# tapegyseg.net
KiCad netlist of a schematic drawn in Altium Designer
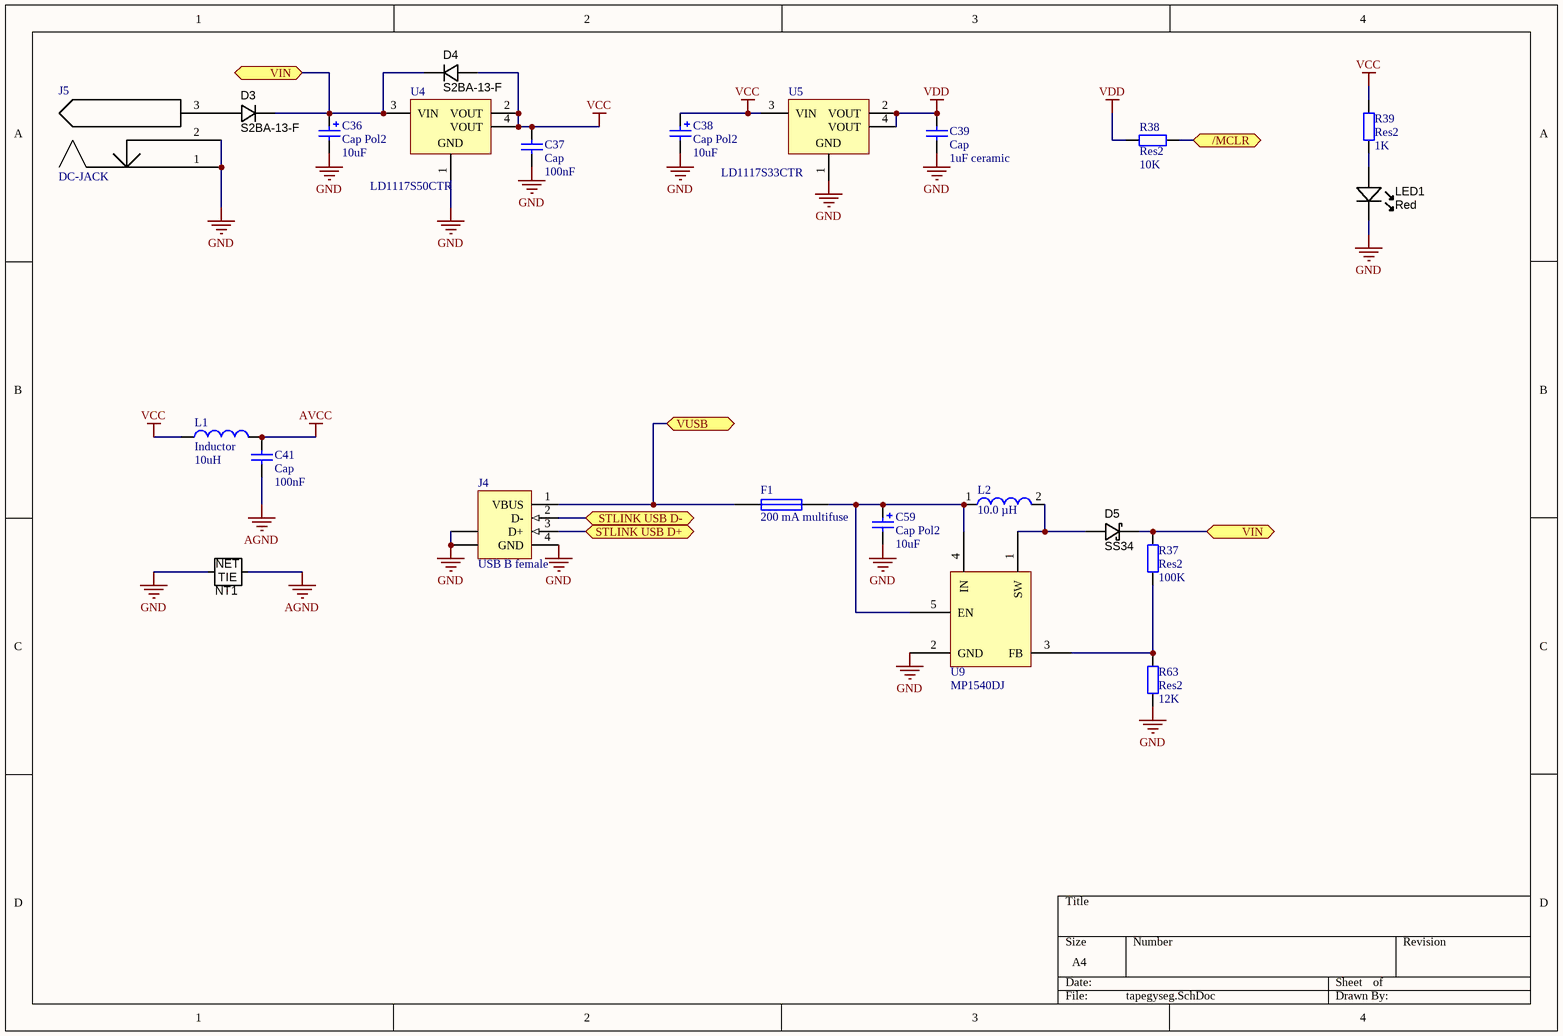
[diagram p0: tapegyseg.SchDoc]

(export (version "E")
  (design (tool "Eeschema 10.0.6"))
  (components
    (comp (ref "C36")
      (value "Cap Pol2")
      (footprint "CAPMP3528X210N")
      (description "Polarized Capacitor (Axial)")
      (fields (field (name "ALTIUM_VALUE") "10uF") (field (name "PUBLISHER") "Altium Limited"))
      (libsource (lib "Miscellaneous Devices") (part "Cap Pol2"))
    )
    (comp (ref "C37")
      (value "Cap")
      (footprint "CAPC2012X135N")
      (description "Capacitor")
      (fields (field (name "ALTIUM_VALUE") "100nF") (field (name "PUBLISHER") "Altium Limited"))
      (libsource (lib "Miscellaneous Devices") (part "Cap"))
    )
    (comp (ref "C38")
      (value "Cap Pol2")
      (footprint "CAPMP3528X210N")
      (description "Polarized Capacitor (Axial)")
      (fields (field (name "ALTIUM_VALUE") "10uF") (field (name "PUBLISHER") "Altium Limited"))
      (libsource (lib "Miscellaneous Devices") (part "Cap Pol2"))
    )
    (comp (ref "C39")
      (value "Cap")
      (footprint "CAPC2012X135N")
      (description "Capacitor")
      (fields (field (name "ALTIUM_VALUE") "1uF ceramic") (field (name "PUBLISHER") "Altium Limited"))
      (libsource (lib "Miscellaneous Devices") (part "Cap"))
    )
    (comp (ref "C41")
      (value "Cap")
      (footprint "CAPC2012X135N")
      (description "Capacitor")
      (fields (field (name "ALTIUM_VALUE") "100nF") (field (name "PUBLISHER") "Altium Limited"))
      (libsource (lib "Miscellaneous Devices") (part "Cap"))
    )
    (comp (ref "C59")
      (value "Cap Pol2")
      (footprint "CAPMP3528X210N")
      (description "Polarized Capacitor (Axial)")
      (fields (field (name "ALTIUM_VALUE") "10uF") (field (name "PUBLISHER") "Altium Limited"))
      (libsource (lib "Miscellaneous Devices") (part "Cap Pol2"))
    )
    (comp (ref "D3")
      (value "100V; 1.5A")
      (footprint "DO-214AC")
      (description "Diode SMD 100V 1.5A SMA")
      (fields (field (name "MANUFACTURER PART NUMBER 1") "S2BA-13-F"))
      (libsource (lib "PBL - Diodes") (part "DIODE_100V_1.5A_SMA"))
    )
    (comp (ref "D4")
      (value "100V; 1.5A")
      (footprint "DO-214AC")
      (description "Diode SMD 100V 1.5A SMA")
      (fields (field (name "MANUFACTURER PART NUMBER 1") "S2BA-13-F"))
      (libsource (lib "PBL - Diodes") (part "DIODE_100V_1.5A_SMA"))
    )
    (comp (ref "D5")
      (value "SS34")
      (footprint "DO-214AA")
      (description "Diode Schottky SMD 30V 2A DO-214AA")
      (libsource (lib "PBL - Diodes") (part "DIODE_SCHOTTKY_MBRS130L"))
    )
    (comp (ref "F1")
      (value "200 mA multifuse")
      (footprint "RESC6332X70N")
      (description "Fuse")
      (fields (field (name "PUBLISHER") "Altium Limited"))
      (libsource (lib "Miscellaneous Devices") (part "Fuse 1"))
    )
    (comp (ref "J4")
      (value "USB B female")
      (footprint "1437106")
      (description "USB 1.1, Right Angle, Thru-Hole, B Type, Receptacle, 4 Position, Natural")
      (fields (field (name "PUBLISHER") "Altium Limited"))
      (libsource (lib "AMP Serial Bus USB") (part "4-1437106-8"))
    )
    (comp (ref "J5")
      (value "DC-JACK")
      (footprint "JACK")
      (description "Tápcsatlakozó")
      (libsource (lib "sajat") (part "DC-JACK"))
    )
    (comp (ref "L1")
      (value "Inductor")
      (footprint "6-0805_N")
      (fields (field (name "ALTIUM_VALUE") "10uH") (field (name "PUBLISHER") "Altium Limited"))
      (libsource (lib "Miscellaneous Devices") (part "Inductor"))
    )
    (comp (ref "L2")
      (value "7447745100")
      (footprint "WE-PD2-MS")
      (description "SMD Power Inductor WE-PD2, L = 10.0 µH")
      (fields (field (name "INDUCTANCE") "10.0 µH"))
      (libsource (lib "Wuerth Elektronik SMD Power Choke") (part "7447745100"))
    )
    (comp (ref "LED1")
      (value "~")
      (footprint "LED-0805-K")
      (description "LED 0805 SMD Red 6mcd 621nm")
      (fields (field (name "COLOR") "Red"))
      (libsource (lib "PBL - Light Sources") (part "LED_SMD_Red_0805_6mcd"))
    )
    (comp (ref "NT1")
      (value "Net Tie")
      (footprint "NetTie_External_24mil")
      (libsource (lib "PBL - Pads and Jumpers") (part "JUMP_NETTIE"))
    )
    (comp (ref "R37")
      (value "Res2")
      (footprint "RESC2012X70N")
      (description "Resistor")
      (fields (field (name "ALTIUM_VALUE") "100K") (field (name "PUBLISHER") "Altium Limited"))
      (libsource (lib "") (part "Res2_1"))
    )
    (comp (ref "R38")
      (value "Res2")
      (footprint "RESC2012X70N")
      (description "Resistor")
      (fields (field (name "ALTIUM_VALUE") "10K") (field (name "PUBLISHER") "Altium Limited"))
      (libsource (lib "Miscellaneous Devices") (part "Res2"))
    )
    (comp (ref "R39")
      (value "Res2")
      (footprint "RESC2012X70N")
      (description "Resistor")
      (fields (field (name "ALTIUM_VALUE") "1K") (field (name "PUBLISHER") "Altium Limited"))
      (libsource (lib "") (part "Res2_1"))
    )
    (comp (ref "R63")
      (value "Res2")
      (footprint "RESC2012X70N")
      (description "Resistor")
      (fields (field (name "ALTIUM_VALUE") "12K") (field (name "PUBLISHER") "Altium Limited"))
      (libsource (lib "") (part "Res2_1"))
    )
    (comp (ref "U4")
      (value "LD1117S50CTR")
      (footprint "SOT-223_M")
      (description "Fixed Low Drop Positive Voltage Regulator, 5V, 4-Pin SOT-223, Tape and Reel")
      (libsource (lib "STMicroelectronics Power Management Linear Regulator") (part "LD1117S50CTR"))
    )
    (comp (ref "U5")
      (value "LD1117S33CTR")
      (footprint "SOT-223_L")
      (description "Fixed Low Drop Positive Voltage Regulator, 3.3V, 4-Pin SOT-223, Tape and Reel")
      (libsource (lib "STMicroelectronics Power Management Linear Regulator") (part "LD1117S33CTR"))
    )
    (comp (ref "U9")
      (value "MP1540DJ")
      (footprint "S5")
      (description "Step-up converter")
      (libsource (lib "sajat") (part "MP1540"))
    )
  )
  (nets
    (net (code "1") (name "/STLINK USB D+") (class "Default")
      (node (ref "J4") (pin "3") (pinfunction "D+_3") (pintype "input"))
    )
    (net (code "2") (name "/STLINK USB D-") (class "Default")
      (node (ref "J4") (pin "2") (pinfunction "D-_2") (pintype "input"))
    )
    (net (code "3") (name "/VIN") (class "Default")
      (node (ref "C36") (pin "1") (pinfunction "1_1") (pintype "passive"))
      (node (ref "D3") (pin "K") (pinfunction "K_K") (pintype "passive"))
      (node (ref "D4") (pin "K") (pinfunction "K_K") (pintype "passive"))
      (node (ref "D5") (pin "K") (pinfunction "K_K") (pintype "passive"))
      (node (ref "R37") (pin "2") (pinfunction "2_2") (pintype "passive"))
      (node (ref "U4") (pin "3") (pinfunction "VIN_3") (pintype "power_in"))
    )
    (net (code "4") (name "/VUSB") (class "Default")
      (node (ref "F1") (pin "1") (pinfunction "1_1") (pintype "passive"))
      (node (ref "J4") (pin "1") (pinfunction "VBUS_1") (pintype "power_in"))
    )
    (net (code "5") (name "/{slash}MCLR") (class "Default")
      (node (ref "R38") (pin "2") (pinfunction "2_2") (pintype "passive"))
    )
    (net (code "6") (name "AGND") (class "Default")
      (node (ref "C41") (pin "1") (pinfunction "1_1") (pintype "passive"))
      (node (ref "NT1") (pin "2") (pinfunction "2_2") (pintype "passive"))
    )
    (net (code "7") (name "AVCC") (class "Default")
      (node (ref "C41") (pin "2") (pinfunction "2_2") (pintype "passive"))
      (node (ref "L1") (pin "2") (pinfunction "2_2") (pintype "passive"))
    )
    (net (code "8") (name "GND") (class "Default")
      (node (ref "C36") (pin "2") (pinfunction "2_2") (pintype "passive"))
      (node (ref "C37") (pin "1") (pinfunction "1_1") (pintype "passive"))
      (node (ref "C38") (pin "2") (pinfunction "2_2") (pintype "passive"))
      (node (ref "C39") (pin "1") (pinfunction "1_1") (pintype "passive"))
      (node (ref "C59") (pin "2") (pinfunction "2_2") (pintype "passive"))
      (node (ref "J4") (pin "4") (pinfunction "GND_4") (pintype "power_in"))
      (node (ref "J4") (pin "5") (pinfunction "SHLD_5") (pintype "passive"))
      (node (ref "J4") (pin "6") (pinfunction "SHLD_6") (pintype "passive"))
      (node (ref "J5") (pin "1") (pinfunction "1_1") (pintype "passive"))
      (node (ref "J5") (pin "2") (pinfunction "2_2") (pintype "passive"))
      (node (ref "LED1") (pin "K") (pinfunction "K_K") (pintype "passive"))
      (node (ref "NT1") (pin "1") (pinfunction "1_1") (pintype "passive"))
      (node (ref "R63") (pin "1") (pinfunction "1_1") (pintype "passive"))
      (node (ref "U4") (pin "1") (pinfunction "GND_1") (pintype "power_in"))
      (node (ref "U5") (pin "1") (pinfunction "GND_1") (pintype "power_in"))
      (node (ref "U9") (pin "2") (pinfunction "GND_2") (pintype "passive"))
    )
    (net (code "9") (name "Net-(D3-PadA)") (class "Default")
      (node (ref "D3") (pin "A") (pinfunction "A_A") (pintype "passive"))
      (node (ref "J5") (pin "3") (pinfunction "3_3") (pintype "passive"))
    )
    (net (code "10") (name "Net-(LED1-PadA)") (class "Default")
      (node (ref "LED1") (pin "A") (pinfunction "A_A") (pintype "passive"))
      (node (ref "R39") (pin "1") (pinfunction "1_1") (pintype "passive"))
    )
    (net (code "11") (name "Net-(U9-EN)") (class "Default")
      (node (ref "C59") (pin "1") (pinfunction "1_1") (pintype "passive"))
      (node (ref "F1") (pin "2") (pinfunction "2_2") (pintype "passive"))
      (node (ref "L2") (pin "1") (pinfunction "1_1") (pintype "passive"))
      (node (ref "U9") (pin "4") (pinfunction "IN_4") (pintype "passive"))
      (node (ref "U9") (pin "5") (pinfunction "EN_5") (pintype "passive"))
    )
    (net (code "12") (name "Net-(U9-FB)") (class "Default")
      (node (ref "R37") (pin "1") (pinfunction "1_1") (pintype "passive"))
      (node (ref "R63") (pin "2") (pinfunction "2_2") (pintype "passive"))
      (node (ref "U9") (pin "3") (pinfunction "FB_3") (pintype "passive"))
    )
    (net (code "13") (name "Net-(U9-SW)") (class "Default")
      (node (ref "D5") (pin "A") (pinfunction "A_A") (pintype "passive"))
      (node (ref "L2") (pin "2") (pinfunction "2_2") (pintype "passive"))
      (node (ref "U9") (pin "1") (pinfunction "SW_1") (pintype "passive"))
    )
    (net (code "14") (name "VCC") (class "Default")
      (node (ref "C37") (pin "2") (pinfunction "2_2") (pintype "passive"))
      (node (ref "C38") (pin "1") (pinfunction "1_1") (pintype "passive"))
      (node (ref "D4") (pin "A") (pinfunction "A_A") (pintype "passive"))
      (node (ref "L1") (pin "1") (pinfunction "1_1") (pintype "passive"))
      (node (ref "R39") (pin "2") (pinfunction "2_2") (pintype "passive"))
      (node (ref "U4") (pin "2") (pinfunction "VOUT_2") (pintype "power_in"))
      (node (ref "U4") (pin "4") (pinfunction "VOUT_4") (pintype "power_in"))
      (node (ref "U5") (pin "3") (pinfunction "VIN_3") (pintype "power_in"))
    )
    (net (code "15") (name "VDD") (class "Default")
      (node (ref "C39") (pin "2") (pinfunction "2_2") (pintype "passive"))
      (node (ref "R38") (pin "1") (pinfunction "1_1") (pintype "passive"))
      (node (ref "U5") (pin "2") (pinfunction "VOUT_2") (pintype "power_in"))
      (node (ref "U5") (pin "4") (pinfunction "VOUT_4") (pintype "power_in"))
    )
  )
)
